# Game_Controller_Rev_1_2.net
KiCad netlist of a schematic drawn in EAGLE
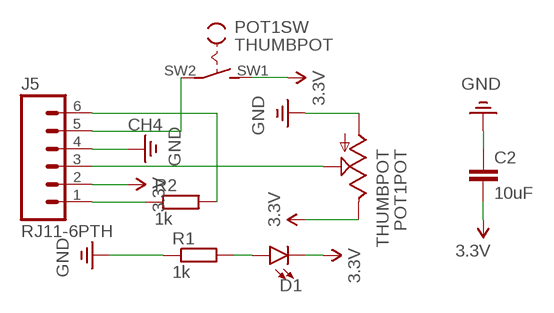
[diagram p0: schematic, sheet 1]

(export (version "E")
  (design (tool "Eeschema 10.0.6"))
  (components
    (comp (ref "C2")
      (value "10uF")
      (footprint "eagle-import:0805")
      (libsource (lib "eagle-import") (part "10UF-0805-10V-10%"))
    )
    (comp (ref "D1")
      (value "LED-3MM-NO_SILK")
      (footprint "eagle-import:LED_3MM-NS")
      (libsource (lib "eagle-import") (part "LED-3MM-NO_SILK"))
    )
    (comp (ref "J5")
      (value "RJ11-6PTH")
      (footprint "eagle-import:RJ11-6")
      (libsource (lib "eagle-import") (part "RJ11-6PTH"))
    )
    (comp (ref "POT1")
      (value "THUMBPOT")
      (footprint "eagle-import:THUMBWHEEL")
      (libsource (lib "eagle-import") (part "THUMBPOT"))
    )
    (comp (ref "R1")
      (value "1k")
      (footprint "eagle-import:M0805")
      (libsource (lib "eagle-import") (part "R-EU_M0805"))
    )
    (comp (ref "R2")
      (value "1k")
      (footprint "eagle-import:M0805")
      (libsource (lib "eagle-import") (part "R-EU_M0805"))
    )
  )
  (nets
    (net (code "1") (name "/CH4") (class "Default")
      (node (ref "J5") (pin "5") (pinfunction "5_5") (pintype "passive"))
      (node (ref "POT1") (pin "SW2") (pinfunction "P_SW2") (pintype "passive"))
    )
    (net (code "2") (name "3.3V") (class "Default")
      (node (ref "C2") (pin "2") (pinfunction "2_2") (pintype "passive"))
      (node (ref "D1") (pin "K") (pinfunction "C_K") (pintype "passive"))
      (node (ref "J5") (pin "2") (pinfunction "2_2") (pintype "passive"))
      (node (ref "POT1") (pin "3") (pinfunction "E_3") (pintype "passive"))
      (node (ref "POT1") (pin "SW1") (pinfunction "S_SW1") (pintype "passive"))
    )
    (net (code "3") (name "GND") (class "Default")
      (node (ref "C2") (pin "1") (pinfunction "1_1") (pintype "passive"))
      (node (ref "J5") (pin "4") (pinfunction "4_4") (pintype "passive"))
      (node (ref "POT1") (pin "1") (pinfunction "A_1") (pintype "passive"))
      (node (ref "R1") (pin "1") (pinfunction "1_1") (pintype "passive"))
    )
    (net (code "4") (name "Net-(D1-PadA)") (class "Default")
      (node (ref "D1") (pin "A") (pinfunction "A_A") (pintype "passive"))
      (node (ref "R1") (pin "2") (pinfunction "2_2") (pintype "passive"))
    )
    (net (code "5") (name "Net-(J5-Pad1)") (class "Default")
      (node (ref "J5") (pin "1") (pinfunction "1_1") (pintype "passive"))
      (node (ref "R2") (pin "1") (pinfunction "1_1") (pintype "passive"))
    )
    (net (code "6") (name "Net-(J5-Pad6)") (class "Default")
      (node (ref "J5") (pin "6") (pinfunction "6_6") (pintype "passive"))
      (node (ref "R2") (pin "2") (pinfunction "2_2") (pintype "passive"))
    )
    (net (code "7") (name "Net-(POT1A-S)") (class "Default")
      (node (ref "J5") (pin "3") (pinfunction "3_3") (pintype "passive"))
      (node (ref "POT1") (pin "2") (pinfunction "S_2") (pintype "passive"))
    )
  )
)
